# RFID_Lock_Rev_1_PCB.net
KiCad netlist of a schematic drawn in EAGLE
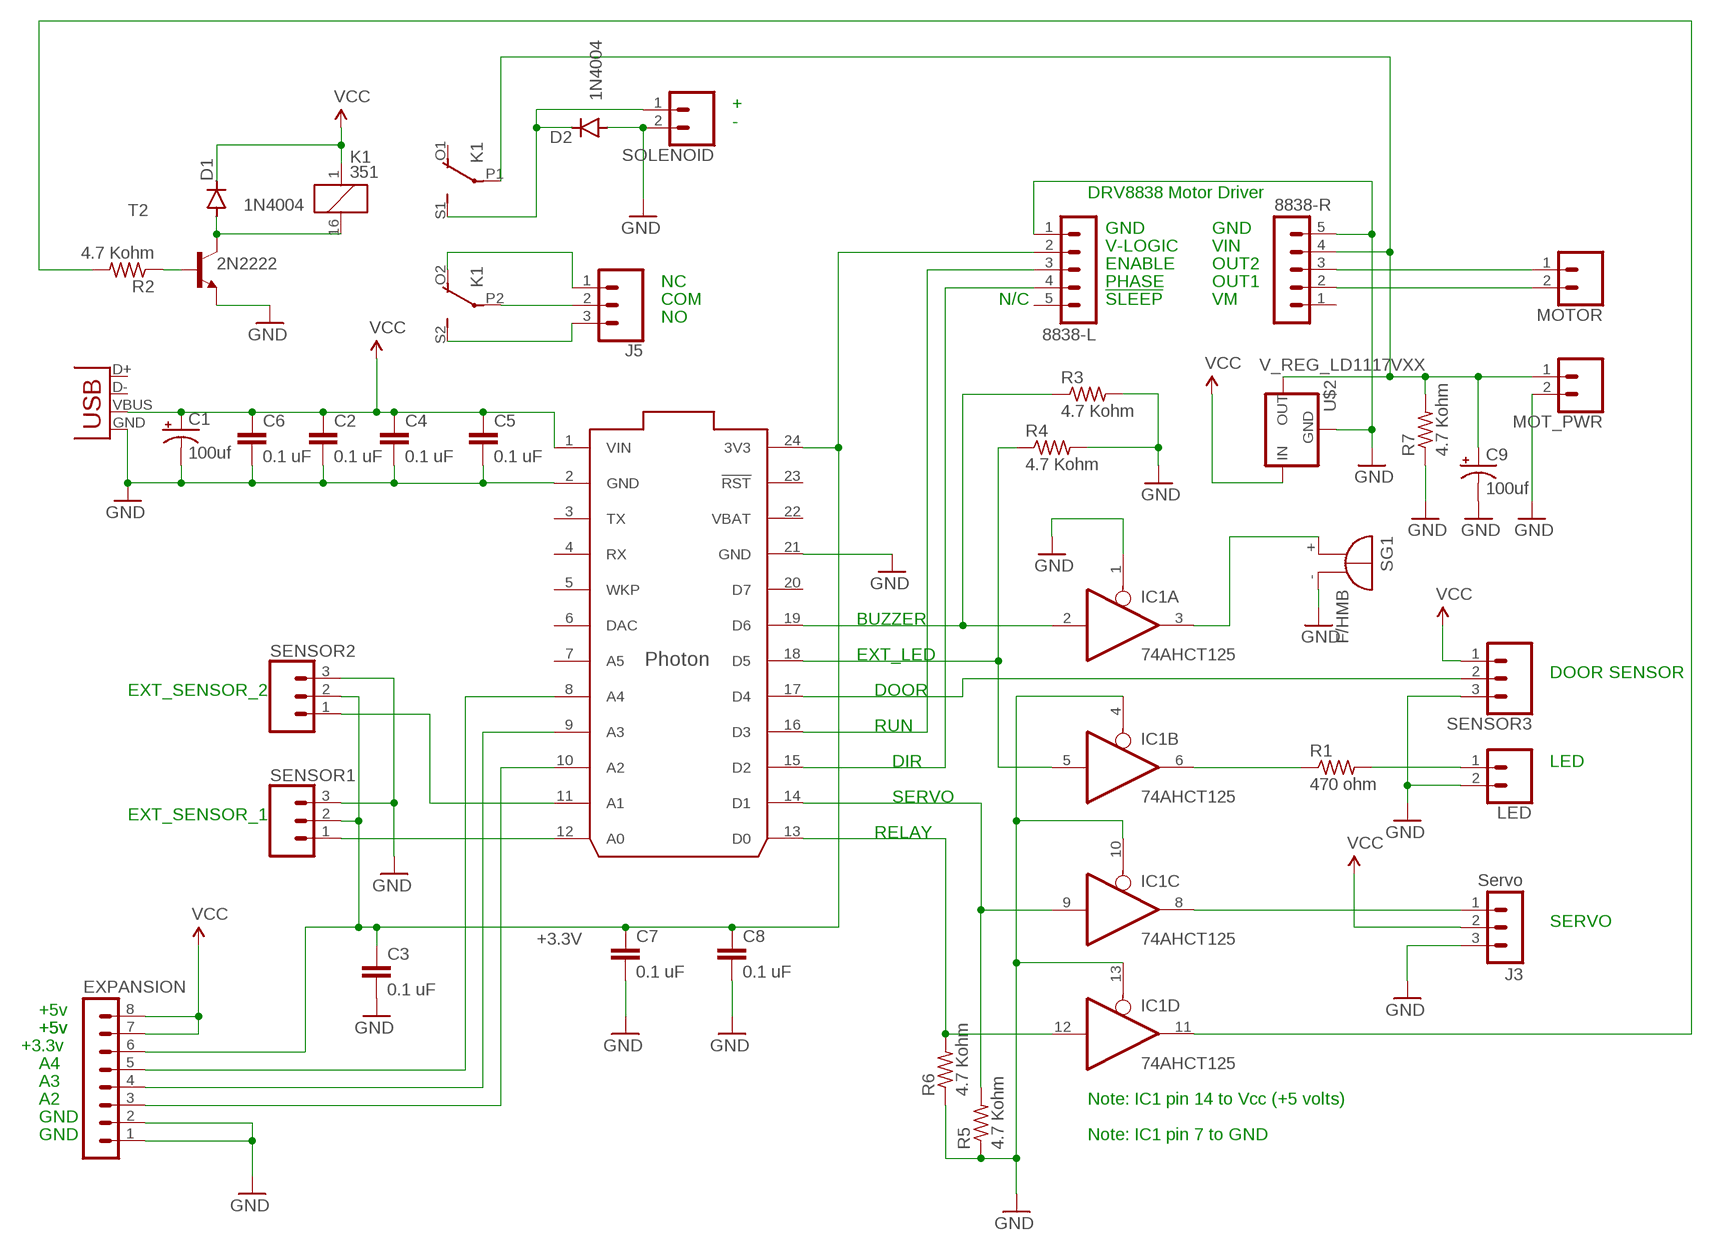
[diagram p0: schematic, sheet 1]

(export (version "E")
  (design (tool "Eeschema 10.0.6"))
  (components
    (comp (ref "8838-L")
      (value "MA05-1")
      (footprint "eagle-import:MA05-1")
      (libsource (lib "eagle-import") (part "MA05-1"))
    )
    (comp (ref "8838-R")
      (value "MA05-1")
      (footprint "eagle-import:MA05-1")
      (libsource (lib "eagle-import") (part "MA05-1"))
    )
    (comp (ref "C1")
      (value "100uf")
      (footprint "eagle-import:CPOL-RADIAL-100UF-25V")
      (libsource (lib "eagle-import") (part "CAP_POLPTH1"))
    )
    (comp (ref "C2")
      (value "0.1 uF")
      (footprint "eagle-import:CAP-PTH-SMALL")
      (libsource (lib "eagle-import") (part "CAPPTH"))
    )
    (comp (ref "C3")
      (value "0.1 uF")
      (footprint "eagle-import:CAP-PTH-SMALL")
      (libsource (lib "eagle-import") (part "CAPPTH"))
    )
    (comp (ref "C4")
      (value "0.1 uF")
      (footprint "eagle-import:CAP-PTH-SMALL")
      (libsource (lib "eagle-import") (part "CAPPTH"))
    )
    (comp (ref "C5")
      (value "0.1 uF")
      (footprint "eagle-import:CAP-PTH-SMALL")
      (libsource (lib "eagle-import") (part "CAPPTH"))
    )
    (comp (ref "C6")
      (value "0.1 uF")
      (footprint "eagle-import:CAP-PTH-SMALL")
      (libsource (lib "eagle-import") (part "CAPPTH"))
    )
    (comp (ref "C7")
      (value "0.1 uF")
      (footprint "eagle-import:CAP-PTH-SMALL")
      (libsource (lib "eagle-import") (part "CAPPTH"))
    )
    (comp (ref "C8")
      (value "0.1 uF")
      (footprint "eagle-import:CAP-PTH-SMALL")
      (libsource (lib "eagle-import") (part "CAPPTH"))
    )
    (comp (ref "C9")
      (value "100uf")
      (footprint "eagle-import:CPOL-RADIAL-100UF-25V")
      (libsource (lib "eagle-import") (part "CAP_POLPTH1"))
    )
    (comp (ref "D1")
      (value "1N4004")
      (footprint "eagle-import:DO41-10")
      (libsource (lib "eagle-import") (part "1N4004"))
    )
    (comp (ref "D2")
      (value "1N4004")
      (footprint "eagle-import:DO41-10")
      (libsource (lib "eagle-import") (part "1N4004"))
    )
    (comp (ref "EXPANSION")
      (value "MA08-1")
      (footprint "eagle-import:MA08-1")
      (libsource (lib "eagle-import") (part "MA08-1"))
    )
    (comp (ref "IC1")
      (value "74AHCT125")
      (footprint "eagle-import:DIL14")
      (libsource (lib "eagle-import") (part "74125N"))
    )
    (comp (ref "J3")
      (value "Servo")
      (footprint "eagle-import:MA03-1")
      (libsource (lib "eagle-import") (part "MA03-1"))
    )
    (comp (ref "J5")
      (value "CONN_03SCREW")
      (footprint "eagle-import:SCREWTERMINAL-3.5MM-3")
      (libsource (lib "eagle-import") (part "CONN_03SCREW"))
    )
    (comp (ref "JP1")
      (value "USB-B")
      (footprint "eagle-import:USB-B-PTH")
      (libsource (lib "eagle-import") (part "USBPTH"))
    )
    (comp (ref "K1")
      (value "351")
      (footprint "eagle-import:351")
      (libsource (lib "eagle-import") (part "351"))
    )
    (comp (ref "LED")
      (value "CONN_023.5MM")
      (footprint "eagle-import:SCREWTERMINAL-3.5MM-2")
      (libsource (lib "eagle-import") (part "CONN_023.5MM"))
    )
    (comp (ref "MOTOR")
      (value "CONN_023.5MM")
      (footprint "eagle-import:SCREWTERMINAL-3.5MM-2")
      (libsource (lib "eagle-import") (part "CONN_023.5MM"))
    )
    (comp (ref "MOT_PWR")
      (value "CONN_023.5MM")
      (footprint "eagle-import:SCREWTERMINAL-3.5MM-2")
      (libsource (lib "eagle-import") (part "CONN_023.5MM"))
    )
    (comp (ref "R1")
      (value "470 ohm")
      (footprint "eagle-import:0309_12")
      (libsource (lib "eagle-import") (part "R-US_0309/12"))
    )
    (comp (ref "R2")
      (value "4.7 Kohm")
      (footprint "eagle-import:0309_12")
      (libsource (lib "eagle-import") (part "R-US_0309/12"))
    )
    (comp (ref "R3")
      (value "4.7 Kohm")
      (footprint "eagle-import:0309_12")
      (libsource (lib "eagle-import") (part "R-US_0309/12"))
    )
    (comp (ref "R4")
      (value "4.7 Kohm")
      (footprint "eagle-import:0309_12")
      (libsource (lib "eagle-import") (part "R-US_0309/12"))
    )
    (comp (ref "R5")
      (value "4.7 Kohm")
      (footprint "eagle-import:0309_12")
      (libsource (lib "eagle-import") (part "R-US_0309/12"))
    )
    (comp (ref "R6")
      (value "4.7 Kohm")
      (footprint "eagle-import:0309_12")
      (libsource (lib "eagle-import") (part "R-US_0309/12"))
    )
    (comp (ref "R7")
      (value "4.7 Kohm")
      (footprint "eagle-import:0309_12")
      (libsource (lib "eagle-import") (part "R-US_0309/12"))
    )
    (comp (ref "SENSOR1")
      (value "CONN_03SCREW")
      (footprint "eagle-import:SCREWTERMINAL-3.5MM-3")
      (libsource (lib "eagle-import") (part "CONN_03SCREW"))
    )
    (comp (ref "SENSOR2")
      (value "CONN_03SCREW")
      (footprint "eagle-import:SCREWTERMINAL-3.5MM-3")
      (libsource (lib "eagle-import") (part "CONN_03SCREW"))
    )
    (comp (ref "SENSOR3")
      (value "CONN_03SCREW")
      (footprint "eagle-import:SCREWTERMINAL-3.5MM-3")
      (libsource (lib "eagle-import") (part "CONN_03SCREW"))
    )
    (comp (ref "SG1")
      (value "F/HMB")
      (footprint "eagle-import:F_HMB")
      (libsource (lib "eagle-import") (part "F/HMB"))
    )
    (comp (ref "SOLENOID")
      (value "CONN_023.5MM")
      (footprint "eagle-import:SCREWTERMINAL-3.5MM-2")
      (libsource (lib "eagle-import") (part "CONN_023.5MM"))
    )
    (comp (ref "T2")
      (value "2N2222")
      (footprint "eagle-import:TO92-EBC-OVAL")
      (libsource (lib "eagle-import") (part "2N2222"))
    )
    (comp (ref "U$1")
      (value "PHOTON_WITH_HEADERS")
      (footprint "eagle-import:PHOTON")
      (libsource (lib "eagle-import") (part "PHOTON_WITH_HEADERS"))
    )
    (comp (ref "U$2")
      (value "V_REG_LD1117VXX")
      (footprint "eagle-import:78XXL")
      (libsource (lib "eagle-import") (part "V_REG_LD1117VXX"))
    )
  )
  (nets
    (net (code "1") (name "/+3.3V") (class "Default")
      (node (ref "8838-L") (pin "2") (pinfunction "2_2") (pintype "passive"))
      (node (ref "C3") (pin "1") (pinfunction "1_1") (pintype "passive"))
      (node (ref "C7") (pin "1") (pinfunction "1_1") (pintype "passive"))
      (node (ref "C8") (pin "1") (pinfunction "1_1") (pintype "passive"))
      (node (ref "EXPANSION") (pin "6") (pinfunction "6_6") (pintype "passive"))
      (node (ref "SENSOR1") (pin "2") (pinfunction "2_2") (pintype "passive"))
      (node (ref "SENSOR2") (pin "2") (pinfunction "2_2") (pintype "passive"))
      (node (ref "U$1") (pin "24") (pinfunction "3V3_24") (pintype "power_in"))
    )
    (net (code "2") (name "/VBAT") (class "Default")
      (node (ref "U$1") (pin "22") (pinfunction "VBAT_22") (pintype "power_in"))
    )
    (net (code "3") (name "GND") (class "Default")
      (node (ref "8838-L") (pin "1") (pinfunction "1_1") (pintype "passive"))
      (node (ref "8838-R") (pin "5") (pinfunction "5_5") (pintype "passive"))
      (node (ref "C1") (pin "2") (pinfunction "-_2") (pintype "passive"))
      (node (ref "C2") (pin "2") (pinfunction "2_2") (pintype "passive"))
      (node (ref "C3") (pin "2") (pinfunction "2_2") (pintype "passive"))
      (node (ref "C4") (pin "2") (pinfunction "2_2") (pintype "passive"))
      (node (ref "C5") (pin "2") (pinfunction "2_2") (pintype "passive"))
      (node (ref "C6") (pin "2") (pinfunction "2_2") (pintype "passive"))
      (node (ref "C7") (pin "2") (pinfunction "2_2") (pintype "passive"))
      (node (ref "C8") (pin "2") (pinfunction "2_2") (pintype "passive"))
      (node (ref "C9") (pin "2") (pinfunction "-_2") (pintype "passive"))
      (node (ref "D2") (pin "A") (pinfunction "A_A") (pintype "passive"))
      (node (ref "EXPANSION") (pin "1") (pinfunction "1_1") (pintype "passive"))
      (node (ref "EXPANSION") (pin "2") (pinfunction "2_2") (pintype "passive"))
      (node (ref "IC1") (pin "1") (pinfunction "OE_1") (pintype "input"))
      (node (ref "IC1") (pin "10") (pinfunction "OE_10") (pintype "input"))
      (node (ref "IC1") (pin "13") (pinfunction "OE_13") (pintype "input"))
      (node (ref "IC1") (pin "4") (pinfunction "OE_4") (pintype "input"))
      (node (ref "J3") (pin "3") (pinfunction "3_3") (pintype "passive"))
      (node (ref "JP1") (pin "GND") (pinfunction "GND_GND") (pintype "bidirectional"))
      (node (ref "LED") (pin "2") (pinfunction "2_2") (pintype "passive"))
      (node (ref "MOT_PWR") (pin "2") (pinfunction "2_2") (pintype "passive"))
      (node (ref "R3") (pin "2") (pinfunction "2_2") (pintype "passive"))
      (node (ref "R4") (pin "2") (pinfunction "2_2") (pintype "passive"))
      (node (ref "R5") (pin "1") (pinfunction "1_1") (pintype "passive"))
      (node (ref "R6") (pin "1") (pinfunction "1_1") (pintype "passive"))
      (node (ref "R7") (pin "1") (pinfunction "1_1") (pintype "passive"))
      (node (ref "SENSOR1") (pin "3") (pinfunction "3_3") (pintype "passive"))
      (node (ref "SENSOR2") (pin "3") (pinfunction "3_3") (pintype "passive"))
      (node (ref "SENSOR3") (pin "3") (pinfunction "3_3") (pintype "passive"))
      (node (ref "SG1") (pin "-") (pinfunction "-_-") (pintype "passive"))
      (node (ref "SOLENOID") (pin "2") (pinfunction "2_2") (pintype "passive"))
      (node (ref "T2") (pin "E") (pinfunction "E_E") (pintype "passive"))
      (node (ref "U$1") (pin "2") (pinfunction "GND_2") (pintype "power_in"))
      (node (ref "U$1") (pin "21") (pinfunction "GND_21") (pintype "power_in"))
      (node (ref "U$2") (pin "IN") (pinfunction "GND_IN") (pintype "input"))
    )
    (net (code "4") (name "Net-(8838-R-Pad2)") (class "Default")
      (node (ref "8838-R") (pin "2") (pinfunction "2_2") (pintype "passive"))
      (node (ref "MOTOR") (pin "2") (pinfunction "2_2") (pintype "passive"))
    )
    (net (code "5") (name "Net-(8838-R-Pad3)") (class "Default")
      (node (ref "8838-R") (pin "3") (pinfunction "3_3") (pintype "passive"))
      (node (ref "MOTOR") (pin "1") (pinfunction "1_1") (pintype "passive"))
    )
    (net (code "6") (name "Net-(C9-+)") (class "Default")
      (node (ref "8838-R") (pin "4") (pinfunction "4_4") (pintype "passive"))
      (node (ref "C9") (pin "1") (pinfunction "+_1") (pintype "passive"))
      (node (ref "K1") (pin "P1") (pinfunction "P_P1") (pintype "passive"))
      (node (ref "MOT_PWR") (pin "1") (pinfunction "1_1") (pintype "passive"))
      (node (ref "R7") (pin "2") (pinfunction "2_2") (pintype "passive"))
      (node (ref "U$2") (pin "GND") (pinfunction "OUT_GND") (pintype "passive"))
    )
    (net (code "7") (name "Net-(IC1A-I)") (class "Default")
      (node (ref "IC1") (pin "2") (pinfunction "I_2") (pintype "input"))
      (node (ref "R3") (pin "1") (pinfunction "1_1") (pintype "passive"))
      (node (ref "U$1") (pin "19") (pinfunction "D6_19") (pintype "bidirectional"))
    )
    (net (code "8") (name "Net-(IC1A-O)") (class "Default")
      (node (ref "IC1") (pin "3") (pinfunction "O_3") (pintype "tri_state"))
      (node (ref "SG1") (pin "+") (pinfunction "+_+") (pintype "passive"))
    )
    (net (code "9") (name "Net-(IC1B-I)") (class "Default")
      (node (ref "IC1") (pin "5") (pinfunction "I_5") (pintype "input"))
      (node (ref "R4") (pin "1") (pinfunction "1_1") (pintype "passive"))
      (node (ref "U$1") (pin "18") (pinfunction "D5_18") (pintype "bidirectional"))
    )
    (net (code "10") (name "Net-(IC1B-O)") (class "Default")
      (node (ref "IC1") (pin "6") (pinfunction "O_6") (pintype "tri_state"))
      (node (ref "R1") (pin "1") (pinfunction "1_1") (pintype "passive"))
    )
    (net (code "11") (name "Net-(IC1C-I)") (class "Default")
      (node (ref "IC1") (pin "9") (pinfunction "I_9") (pintype "input"))
      (node (ref "R5") (pin "2") (pinfunction "2_2") (pintype "passive"))
      (node (ref "U$1") (pin "14") (pinfunction "D1_14") (pintype "bidirectional"))
    )
    (net (code "12") (name "Net-(IC1C-O)") (class "Default")
      (node (ref "IC1") (pin "8") (pinfunction "O_8") (pintype "tri_state"))
      (node (ref "J3") (pin "1") (pinfunction "1_1") (pintype "passive"))
    )
    (net (code "13") (name "Net-(IC1D-I)") (class "Default")
      (node (ref "IC1") (pin "12") (pinfunction "I_12") (pintype "input"))
      (node (ref "R6") (pin "2") (pinfunction "2_2") (pintype "passive"))
      (node (ref "U$1") (pin "13") (pinfunction "D0_13") (pintype "bidirectional"))
    )
    (net (code "14") (name "Net-(IC1D-O)") (class "Default")
      (node (ref "IC1") (pin "11") (pinfunction "O_11") (pintype "tri_state"))
      (node (ref "R2") (pin "2") (pinfunction "2_2") (pintype "passive"))
    )
    (net (code "15") (name "Net-(K1A-2)") (class "Default")
      (node (ref "D1") (pin "A") (pinfunction "A_A") (pintype "passive"))
      (node (ref "K1") (pin "16") (pinfunction "2_16") (pintype "passive"))
      (node (ref "T2") (pin "C") (pinfunction "C_C") (pintype "passive"))
    )
    (net (code "16") (name "Net-(K1B-S)") (class "Default")
      (node (ref "D2") (pin "C") (pinfunction "C_C") (pintype "passive"))
      (node (ref "K1") (pin "S1") (pinfunction "S_S1") (pintype "passive"))
      (node (ref "SOLENOID") (pin "1") (pinfunction "1_1") (pintype "passive"))
    )
    (net (code "17") (name "Net-(K1C-O)") (class "Default")
      (node (ref "J5") (pin "1") (pinfunction "1_1") (pintype "passive"))
      (node (ref "K1") (pin "O2") (pinfunction "O_O2") (pintype "passive"))
    )
    (net (code "18") (name "Net-(K1C-P)") (class "Default")
      (node (ref "J5") (pin "2") (pinfunction "2_2") (pintype "passive"))
      (node (ref "K1") (pin "P2") (pinfunction "P_P2") (pintype "passive"))
    )
    (net (code "19") (name "Net-(K1C-S)") (class "Default")
      (node (ref "J5") (pin "3") (pinfunction "3_3") (pintype "passive"))
      (node (ref "K1") (pin "S2") (pinfunction "S_S2") (pintype "passive"))
    )
    (net (code "20") (name "Net-(LED-Pad1)") (class "Default")
      (node (ref "LED") (pin "1") (pinfunction "1_1") (pintype "passive"))
      (node (ref "R1") (pin "2") (pinfunction "2_2") (pintype "passive"))
    )
    (net (code "21") (name "Net-(R2-Pad1)") (class "Default")
      (node (ref "R2") (pin "1") (pinfunction "1_1") (pintype "passive"))
      (node (ref "T2") (pin "B") (pinfunction "B_B") (pintype "passive"))
    )
    (net (code "22") (name "Net-(U$1-A0)") (class "Default")
      (node (ref "SENSOR1") (pin "1") (pinfunction "1_1") (pintype "passive"))
      (node (ref "U$1") (pin "12") (pinfunction "A0_12") (pintype "bidirectional"))
    )
    (net (code "23") (name "Net-(U$1-A1)") (class "Default")
      (node (ref "SENSOR2") (pin "1") (pinfunction "1_1") (pintype "passive"))
      (node (ref "U$1") (pin "11") (pinfunction "A1_11") (pintype "bidirectional"))
    )
    (net (code "24") (name "Net-(U$1-A2)") (class "Default")
      (node (ref "EXPANSION") (pin "3") (pinfunction "3_3") (pintype "passive"))
      (node (ref "U$1") (pin "10") (pinfunction "A2_10") (pintype "bidirectional"))
    )
    (net (code "25") (name "Net-(U$1-A3)") (class "Default")
      (node (ref "EXPANSION") (pin "4") (pinfunction "4_4") (pintype "passive"))
      (node (ref "U$1") (pin "9") (pinfunction "A3_9") (pintype "bidirectional"))
    )
    (net (code "26") (name "Net-(U$1-A4)") (class "Default")
      (node (ref "EXPANSION") (pin "5") (pinfunction "5_5") (pintype "passive"))
      (node (ref "U$1") (pin "8") (pinfunction "A4_8") (pintype "bidirectional"))
    )
    (net (code "27") (name "Net-(U$1-D2)") (class "Default")
      (node (ref "8838-L") (pin "4") (pinfunction "4_4") (pintype "passive"))
      (node (ref "U$1") (pin "15") (pinfunction "D2_15") (pintype "bidirectional"))
    )
    (net (code "28") (name "Net-(U$1-D3)") (class "Default")
      (node (ref "8838-L") (pin "3") (pinfunction "3_3") (pintype "passive"))
      (node (ref "U$1") (pin "16") (pinfunction "D3_16") (pintype "bidirectional"))
    )
    (net (code "29") (name "Net-(U$1-D4)") (class "Default")
      (node (ref "SENSOR3") (pin "2") (pinfunction "2_2") (pintype "passive"))
      (node (ref "U$1") (pin "17") (pinfunction "D4_17") (pintype "bidirectional"))
    )
    (net (code "30") (name "VCC") (class "Default")
      (node (ref "C1") (pin "1") (pinfunction "+_1") (pintype "passive"))
      (node (ref "C2") (pin "1") (pinfunction "1_1") (pintype "passive"))
      (node (ref "C4") (pin "1") (pinfunction "1_1") (pintype "passive"))
      (node (ref "C5") (pin "1") (pinfunction "1_1") (pintype "passive"))
      (node (ref "C6") (pin "1") (pinfunction "1_1") (pintype "passive"))
      (node (ref "D1") (pin "C") (pinfunction "C_C") (pintype "passive"))
      (node (ref "EXPANSION") (pin "7") (pinfunction "7_7") (pintype "passive"))
      (node (ref "EXPANSION") (pin "8") (pinfunction "8_8") (pintype "passive"))
      (node (ref "J3") (pin "2") (pinfunction "2_2") (pintype "passive"))
      (node (ref "JP1") (pin "VBUS") (pinfunction "VBUS_VBUS") (pintype "bidirectional"))
      (node (ref "K1") (pin "1") (pinfunction "1_1") (pintype "passive"))
      (node (ref "SENSOR3") (pin "1") (pinfunction "1_1") (pintype "passive"))
      (node (ref "U$1") (pin "1") (pinfunction "VIN_1") (pintype "power_in"))
      (node (ref "U$2") (pin "OUT") (pinfunction "IN_OUT") (pintype "input"))
    )
    (net (code "31") (name "unconnected-(8838-L-Pad5)") (class "Default")
      (node (ref "8838-L") (pin "5") (pinfunction "5_5") (pintype "passive"))
    )
    (net (code "32") (name "unconnected-(8838-R-Pad1)") (class "Default")
      (node (ref "8838-R") (pin "1") (pinfunction "1_1") (pintype "passive"))
    )
    (net (code "33") (name "unconnected-(JP1-PadD+)") (class "Default")
      (node (ref "JP1") (pin "D+") (pinfunction "D+_D+") (pintype "bidirectional"))
    )
    (net (code "34") (name "unconnected-(JP1-PadD-)") (class "Default")
      (node (ref "JP1") (pin "D-") (pinfunction "D-_D-") (pintype "bidirectional"))
    )
    (net (code "35") (name "unconnected-(K1B-O-PadO1)") (class "Default")
      (node (ref "K1") (pin "O1") (pinfunction "O_O1") (pintype "passive"))
    )
    (net (code "36") (name "unconnected-(U$1-A5-Pad7)") (class "Default")
      (node (ref "U$1") (pin "7") (pinfunction "A5_7") (pintype "bidirectional"))
    )
    (net (code "37") (name "unconnected-(U$1-D7-Pad20)") (class "Default")
      (node (ref "U$1") (pin "20") (pinfunction "D7_20") (pintype "bidirectional"))
    )
    (net (code "38") (name "unconnected-(U$1-DAC-Pad6)") (class "Default")
      (node (ref "U$1") (pin "6") (pinfunction "DAC_6") (pintype "bidirectional"))
    )
    (net (code "39") (name "unconnected-(U$1-RX-Pad4)") (class "Default")
      (node (ref "U$1") (pin "4") (pinfunction "RX_4") (pintype "bidirectional"))
    )
    (net (code "40") (name "unconnected-(U$1-TX-Pad3)") (class "Default")
      (node (ref "U$1") (pin "3") (pinfunction "TX_3") (pintype "bidirectional"))
    )
    (net (code "41") (name "unconnected-(U$1-WKP-Pad5)") (class "Default")
      (node (ref "U$1") (pin "5") (pinfunction "WKP_5") (pintype "bidirectional"))
    )
    (net (code "42") (name "unconnected-(U$1-~{RST}-Pad23)") (class "Default")
      (node (ref "U$1") (pin "23") (pinfunction "~{RST}_23") (pintype "bidirectional"))
    )
  )
)
